# HB-WDS100-C6-O-2_Main_v2p0.net
KiCad netlist of a schematic drawn in EAGLE
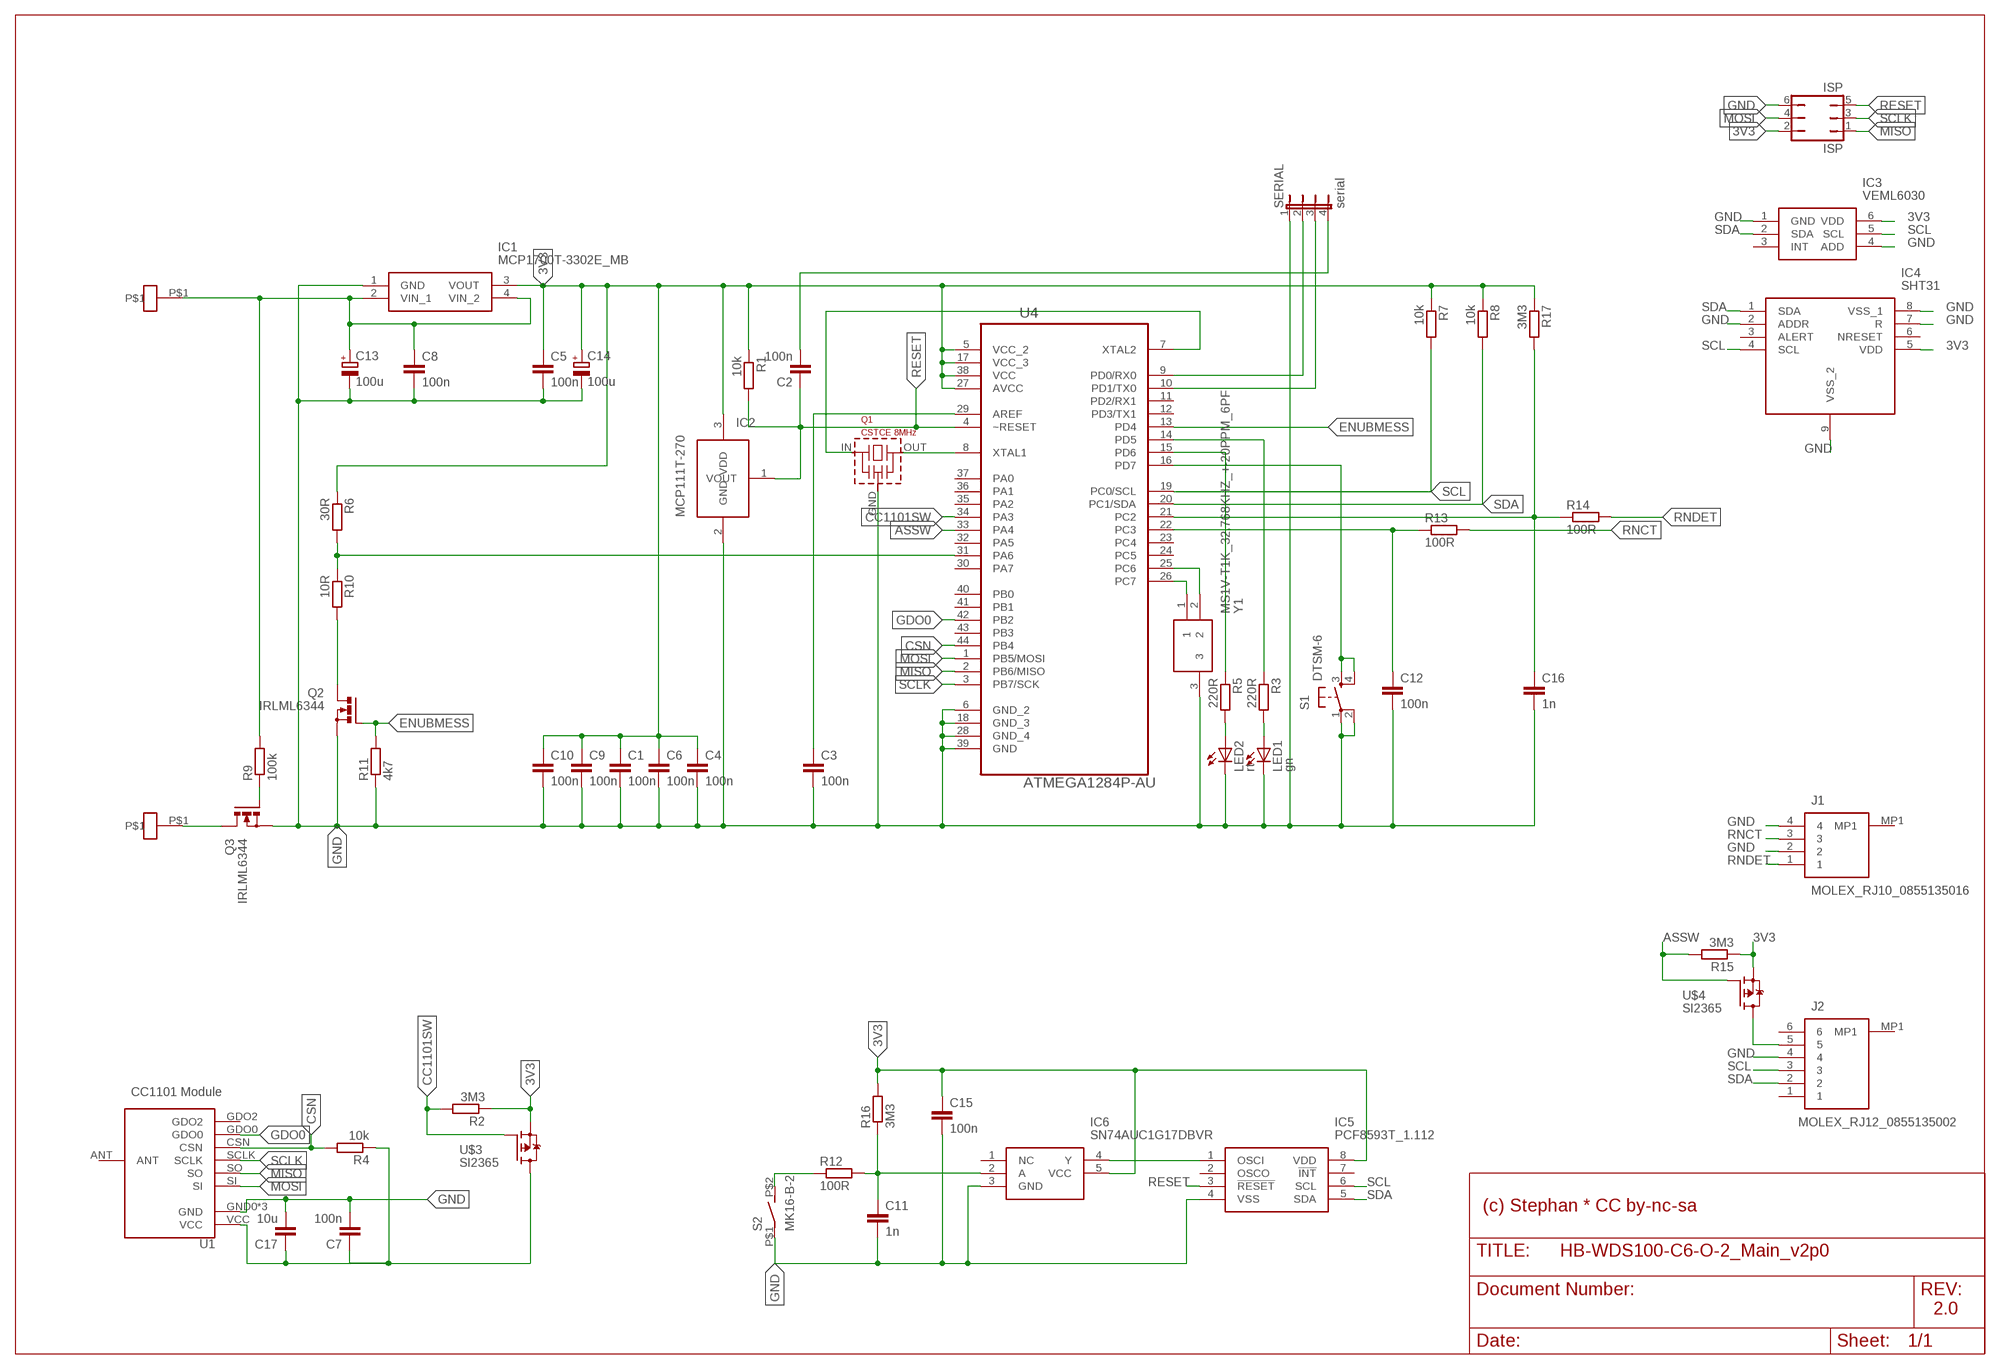
[diagram p0: schematic, sheet 1]

(export (version "E")
  (design (tool "Eeschema 10.0.6"))
  (components
    (comp (ref "C1")
      (value "100n")
      (footprint "eagle-import:C0805K")
      (libsource (lib "eagle-import") (part "resistor_348_C-EUC0805K"))
    )
    (comp (ref "C2")
      (value "100n")
      (footprint "eagle-import:C0805K")
      (libsource (lib "eagle-import") (part "resistor_348_C-EUC0805K"))
    )
    (comp (ref "C3")
      (value "100n")
      (footprint "eagle-import:C0805K")
      (libsource (lib "eagle-import") (part "resistor_348_C-EUC0805K"))
    )
    (comp (ref "C4")
      (value "100n")
      (footprint "eagle-import:C0805K")
      (libsource (lib "eagle-import") (part "resistor_348_C-EUC0805K"))
    )
    (comp (ref "C5")
      (value "100n")
      (footprint "eagle-import:C0805K")
      (libsource (lib "eagle-import") (part "C-EUC0805K"))
    )
    (comp (ref "C6")
      (value "100n")
      (footprint "eagle-import:C0805K")
      (libsource (lib "eagle-import") (part "resistor_348_C-EUC0805K"))
    )
    (comp (ref "C7")
      (value "100n")
      (footprint "eagle-import:C0805K")
      (libsource (lib "eagle-import") (part "resistor_348_C-EUC0805K"))
    )
    (comp (ref "C8")
      (value "100n")
      (footprint "eagle-import:C0805K")
      (libsource (lib "eagle-import") (part "C-EUC0805K"))
    )
    (comp (ref "C9")
      (value "100n")
      (footprint "eagle-import:C0805K")
      (libsource (lib "eagle-import") (part "resistor_348_C-EUC0805K"))
    )
    (comp (ref "C10")
      (value "100n")
      (footprint "eagle-import:C0805K")
      (libsource (lib "eagle-import") (part "resistor_348_C-EUC0805K"))
    )
    (comp (ref "C11")
      (value "1n")
      (footprint "eagle-import:C0805K")
      (libsource (lib "eagle-import") (part "resistor_348_C-EUC0805K"))
    )
    (comp (ref "C12")
      (value "100n")
      (footprint "eagle-import:C0805K")
      (libsource (lib "eagle-import") (part "resistor_348_C-EUC0805K"))
    )
    (comp (ref "C13")
      (value "100u")
      (footprint "eagle-import:CT3528")
      (libsource (lib "eagle-import") (part "CPOL-EUCT3528"))
    )
    (comp (ref "C14")
      (value "100u")
      (footprint "eagle-import:CT3528")
      (libsource (lib "eagle-import") (part "CPOL-EUCT3528"))
    )
    (comp (ref "C15")
      (value "100n")
      (footprint "eagle-import:C0805K")
      (libsource (lib "eagle-import") (part "resistor_348_C-EUC0805K"))
    )
    (comp (ref "C16")
      (value "1n")
      (footprint "eagle-import:C0805K")
      (libsource (lib "eagle-import") (part "resistor_348_C-EUC0805K"))
    )
    (comp (ref "C17")
      (value "10u")
      (footprint "eagle-import:C0805K")
      (libsource (lib "eagle-import") (part "resistor_348_C-EUC0805K"))
    )
    (comp (ref "IC1")
      (value "MCP1700T-3302E_MB")
      (footprint "eagle-import:MCP1700T-3302E_MB")
      (fields
        (field (name "ARROW_PART_NUMBER") "MCP1700T-3302E/MB")
        (field (name "MOUSER_PART_NUMBER") "579-MCP1700T3302E/MB")
      )
      (libsource (lib "eagle-import") (part "MCP1700T-3302E_MB"))
    )
    (comp (ref "IC2")
      (value "MCP111-270")
      (footprint "eagle-import:SOT23")
      (libsource (lib "eagle-import") (part "MCP111T"))
    )
    (comp (ref "IC3")
      (value "VEML6030")
      (footprint "eagle-import:VEML6030-HANDSOLD")
      (fields (field (name "MOUSER_PART_NUMBER") "78-VEML6030"))
      (libsource (lib "eagle-import") (part "VEML6030-HANDSOLD"))
    )
    (comp (ref "IC4")
      (value "SHT31")
      (footprint "eagle-import:SON50P250X250X90-9N-HANDSOLD")
      (fields
        (field (name "ARROW_PART_NUMBER") "SHT31-DIS-F2.5KS")
        (field (name "MANUFACTURER_PART_NUMBER") "SHT31-DIS-F2.5kS")
        (field (name "MOUSER_PART_NUMBER") "403-SHT31-DIS-F")
      )
      (libsource (lib "eagle-import") (part "SHT31-HANDSOLD"))
    )
    (comp (ref "IC5")
      (value "PCF8593T_1.112")
      (footprint "eagle-import:SOIC127P600X175-8N")
      (fields (field (name "MANUFACTURER_PART_NUMBER") "PCF8593T/1.112"))
      (libsource (lib "eagle-import") (part "PCF8593T_1.112"))
    )
    (comp (ref "IC6")
      (value "SN74AUC1G17DBVR")
      (footprint "eagle-import:SOT95P280X145-5N")
      (fields (field (name "MOUSER_PART_NUMBER") "595-SN74AUC1G17DBVR"))
      (libsource (lib "eagle-import") (part "SN74AUC1G17DBVR"))
    )
    (comp (ref "ISP")
      (value "ISP")
      (footprint "eagle-import:JP3Q")
      (libsource (lib "eagle-import") (part "JP3Q"))
    )
    (comp (ref "J1")
      (value "MOLEX_RJ10_0855135016")
      (footprint "eagle-import:MOLEX_RJ10_0855135016")
      (libsource (lib "eagle-import") (part "MOLEX_RJ10_0855135016"))
    )
    (comp (ref "J2")
      (value "MOLEX_RJ12_0855135002")
      (footprint "eagle-import:MOLEX_RJ12_0855135002")
      (fields (field (name "ARROW_PART_NUMBER") "0855135002"))
      (libsource (lib "eagle-import") (part "MOLEX_RJ12_0855135002"))
    )
    (comp (ref "LED1")
      (value "gn")
      (footprint "eagle-import:CHIPLED_0805")
      (libsource (lib "eagle-import") (part "LEDCHIPLED_0805"))
    )
    (comp (ref "LED2")
      (value "rt")
      (footprint "eagle-import:CHIPLED_0805")
      (libsource (lib "eagle-import") (part "LEDCHIPLED_0805"))
    )
    (comp (ref "Q1")
      (value "CSTCE 8MHz")
      (footprint "eagle-import:CSTCE")
      (libsource (lib "eagle-import") (part "CSTCE"))
    )
    (comp (ref "Q2")
      (value "IRLML6344")
      (footprint "eagle-import:SOT-23")
      (libsource (lib "eagle-import") (part "IRLML6344"))
    )
    (comp (ref "Q3")
      (value "IRLML6344")
      (footprint "eagle-import:SOT-23")
      (libsource (lib "eagle-import") (part "IRLML6344"))
    )
    (comp (ref "R1")
      (value "10k")
      (footprint "eagle-import:R0805W")
      (libsource (lib "eagle-import") (part "R-EU_R0805W"))
    )
    (comp (ref "R2")
      (value "3M3")
      (footprint "eagle-import:R0805W")
      (libsource (lib "eagle-import") (part "R-EU_R0805W"))
    )
    (comp (ref "R3")
      (value "220R")
      (footprint "eagle-import:R0805W")
      (libsource (lib "eagle-import") (part "R-EU_R0805W"))
    )
    (comp (ref "R4")
      (value "10k")
      (footprint "eagle-import:R0805W")
      (libsource (lib "eagle-import") (part "R-EU_R0805W"))
    )
    (comp (ref "R5")
      (value "220R")
      (footprint "eagle-import:R0805W")
      (libsource (lib "eagle-import") (part "R-EU_R0805W"))
    )
    (comp (ref "R6")
      (value "30R")
      (footprint "eagle-import:R0805W")
      (libsource (lib "eagle-import") (part "R-EU_R0805W"))
    )
    (comp (ref "R7")
      (value "10k")
      (footprint "eagle-import:R0805W")
      (libsource (lib "eagle-import") (part "R-EU_R0805W"))
    )
    (comp (ref "R8")
      (value "10k")
      (footprint "eagle-import:R0805W")
      (libsource (lib "eagle-import") (part "R-EU_R0805W"))
    )
    (comp (ref "R9")
      (value "100k")
      (footprint "eagle-import:R0805W")
      (libsource (lib "eagle-import") (part "R-EU_R0805W"))
    )
    (comp (ref "R10")
      (value "10R")
      (footprint "eagle-import:R0805W")
      (libsource (lib "eagle-import") (part "R-EU_R0805W"))
    )
    (comp (ref "R11")
      (value "4k7")
      (footprint "eagle-import:R0805W")
      (libsource (lib "eagle-import") (part "R-EU_R0805W"))
    )
    (comp (ref "R12")
      (value "100R")
      (footprint "eagle-import:R0805W")
      (libsource (lib "eagle-import") (part "R-EU_R0805W"))
    )
    (comp (ref "R13")
      (value "100R")
      (footprint "eagle-import:R0805W")
      (libsource (lib "eagle-import") (part "R-EU_R0805W"))
    )
    (comp (ref "R14")
      (value "100R")
      (footprint "eagle-import:R0805W")
      (libsource (lib "eagle-import") (part "R-EU_R0805W"))
    )
    (comp (ref "R15")
      (value "3M3")
      (footprint "eagle-import:R0805W")
      (libsource (lib "eagle-import") (part "R-EU_R0805W"))
    )
    (comp (ref "R16")
      (value "3M3")
      (footprint "eagle-import:R0805W")
      (libsource (lib "eagle-import") (part "R-EU_R0805W"))
    )
    (comp (ref "R17")
      (value "3M3")
      (footprint "eagle-import:R0805W")
      (libsource (lib "eagle-import") (part "R-EU_R0805W"))
    )
    (comp (ref "S1")
      (value "DTSM-6")
      (footprint "eagle-import:DTSM-6")
      (libsource (lib "eagle-import") (part "DTSM-6"))
    )
    (comp (ref "S2")
      (value "MK16-B-2")
      (footprint "eagle-import:MK16-B-2")
      (libsource (lib "eagle-import") (part "MK16-B-2"))
    )
    (comp (ref "SERIAL")
      (value "serial")
      (footprint "eagle-import:JP4")
      (libsource (lib "eagle-import") (part "JP4E"))
    )
    (comp (ref "U$1")
      (value "LOETOESE")
      (footprint "eagle-import:LOETOESE")
      (libsource (lib "eagle-import") (part "LOETOESE"))
    )
    (comp (ref "U$2")
      (value "LOETOESE")
      (footprint "eagle-import:LOETOESE")
      (libsource (lib "eagle-import") (part "LOETOESE"))
    )
    (comp (ref "U$3")
      (value "SI2365")
      (footprint "eagle-import:SOT23")
      (libsource (lib "eagle-import") (part "SI2323"))
    )
    (comp (ref "U$4")
      (value "SI2365")
      (footprint "eagle-import:SOT23")
      (libsource (lib "eagle-import") (part "SI2323"))
    )
    (comp (ref "U1")
      (value "CC1101CC1101-SMD-2MM")
      (footprint "eagle-import:CC1101-SMD2MM")
      (libsource (lib "eagle-import") (part "CC1101CC1101-SMD-2MM"))
    )
    (comp (ref "U4")
      (value "ATMEGA1284P-AU")
      (footprint "eagle-import:QFP80P1200X1200X120-44N")
      (libsource (lib "eagle-import") (part "ATMEGA1284P-AU"))
    )
    (comp (ref "Y1")
      (value "MS1V-T1K_32.768KHZ_+-20PPM_6PF")
      (footprint "eagle-import:MS1VT1K32768KHZ20PPM6PF")
      (fields (field (name "MANUFACTURER_PART_NUMBER") "MS1V-T1K 32.768KHZ +-20PPM 6PF"))
      (libsource (lib "eagle-import") (part "MS1V-T1K_32.768KHZ_+-20PPM_6PF"))
    )
  )
  (nets
    (net (code "1") (name "3V3") (class "Default")
      (node (ref "C1") (pin "1") (pinfunction "1_1") (pintype "passive"))
      (node (ref "C10") (pin "1") (pinfunction "1_1") (pintype "passive"))
      (node (ref "C14") (pin "+") (pinfunction "+_+") (pintype "passive"))
      (node (ref "C15") (pin "1") (pinfunction "1_1") (pintype "passive"))
      (node (ref "C4") (pin "1") (pinfunction "1_1") (pintype "passive"))
      (node (ref "C5") (pin "1") (pinfunction "1_1") (pintype "passive"))
      (node (ref "C6") (pin "1") (pinfunction "1_1") (pintype "passive"))
      (node (ref "C9") (pin "1") (pinfunction "1_1") (pintype "passive"))
      (node (ref "IC1") (pin "3") (pinfunction "VOUT_3") (pintype "output"))
      (node (ref "IC2") (pin "3") (pinfunction "VDD_3") (pintype "power_in"))
      (node (ref "IC3") (pin "6") (pinfunction "VDD_6") (pintype "bidirectional"))
      (node (ref "IC4") (pin "5") (pinfunction "VDD_5") (pintype "power_in"))
      (node (ref "IC5") (pin "8") (pinfunction "VDD_8") (pintype "bidirectional"))
      (node (ref "IC6") (pin "5") (pinfunction "VCC_5") (pintype "power_in"))
      (node (ref "ISP") (pin "2") (pinfunction "2_2") (pintype "passive"))
      (node (ref "R1") (pin "1") (pinfunction "1_1") (pintype "passive"))
      (node (ref "R15") (pin "1") (pinfunction "1_1") (pintype "passive"))
      (node (ref "R16") (pin "2") (pinfunction "2_2") (pintype "passive"))
      (node (ref "R17") (pin "1") (pinfunction "1_1") (pintype "passive"))
      (node (ref "R2") (pin "1") (pinfunction "1_1") (pintype "passive"))
      (node (ref "R6") (pin "1") (pinfunction "1_1") (pintype "passive"))
      (node (ref "R7") (pin "1") (pinfunction "1_1") (pintype "passive"))
      (node (ref "R8") (pin "1") (pinfunction "1_1") (pintype "passive"))
      (node (ref "U$3") (pin "2") (pinfunction "S_2") (pintype "passive"))
      (node (ref "U$4") (pin "2") (pinfunction "S_2") (pintype "passive"))
      (node (ref "U4") (pin "17") (pinfunction "VCC_3_17") (pintype "power_in"))
      (node (ref "U4") (pin "27") (pinfunction "AVCC_27") (pintype "power_in"))
      (node (ref "U4") (pin "38") (pinfunction "VCC_38") (pintype "power_in"))
      (node (ref "U4") (pin "5") (pinfunction "VCC_2_5") (pintype "power_in"))
    )
    (net (code "2") (name "ASSW") (class "Default")
      (node (ref "R15") (pin "2") (pinfunction "2_2") (pintype "passive"))
      (node (ref "U$4") (pin "1") (pinfunction "G_1") (pintype "passive"))
      (node (ref "U4") (pin "33") (pinfunction "PA4_33") (pintype "bidirectional"))
    )
    (net (code "3") (name "CC1101SW") (class "Default")
      (node (ref "R2") (pin "2") (pinfunction "2_2") (pintype "passive"))
      (node (ref "U$3") (pin "1") (pinfunction "G_1") (pintype "passive"))
      (node (ref "U4") (pin "34") (pinfunction "PA3_34") (pintype "bidirectional"))
    )
    (net (code "4") (name "CSN") (class "Default")
      (node (ref "R4") (pin "2") (pinfunction "2_2") (pintype "passive"))
      (node (ref "U1") (pin "CSN") (pinfunction "CSN_CSN") (pintype "bidirectional"))
      (node (ref "U4") (pin "44") (pinfunction "PB4_44") (pintype "bidirectional"))
    )
    (net (code "5") (name "ENUBMESS") (class "Default")
      (node (ref "Q2") (pin "P1") (pinfunction "G_P1") (pintype "passive"))
      (node (ref "R11") (pin "2") (pinfunction "2_2") (pintype "passive"))
      (node (ref "U4") (pin "13") (pinfunction "PD4_13") (pintype "bidirectional"))
    )
    (net (code "6") (name "GDO0") (class "Default")
      (node (ref "U1") (pin "GDO0") (pinfunction "GDO0_GDO0") (pintype "output"))
      (node (ref "U4") (pin "42") (pinfunction "PB2_42") (pintype "bidirectional"))
    )
    (net (code "7") (name "GND") (class "Default")
      (node (ref "C1") (pin "2") (pinfunction "2_2") (pintype "passive"))
      (node (ref "C10") (pin "2") (pinfunction "2_2") (pintype "passive"))
      (node (ref "C11") (pin "2") (pinfunction "2_2") (pintype "passive"))
      (node (ref "C12") (pin "2") (pinfunction "2_2") (pintype "passive"))
      (node (ref "C13") (pin "-") (pinfunction "-_-") (pintype "passive"))
      (node (ref "C14") (pin "-") (pinfunction "-_-") (pintype "passive"))
      (node (ref "C15") (pin "2") (pinfunction "2_2") (pintype "passive"))
      (node (ref "C16") (pin "2") (pinfunction "2_2") (pintype "passive"))
      (node (ref "C17") (pin "2") (pinfunction "2_2") (pintype "passive"))
      (node (ref "C3") (pin "2") (pinfunction "2_2") (pintype "passive"))
      (node (ref "C4") (pin "2") (pinfunction "2_2") (pintype "passive"))
      (node (ref "C5") (pin "2") (pinfunction "2_2") (pintype "passive"))
      (node (ref "C6") (pin "2") (pinfunction "2_2") (pintype "passive"))
      (node (ref "C7") (pin "2") (pinfunction "2_2") (pintype "passive"))
      (node (ref "C8") (pin "2") (pinfunction "2_2") (pintype "passive"))
      (node (ref "C9") (pin "2") (pinfunction "2_2") (pintype "passive"))
      (node (ref "IC1") (pin "1") (pinfunction "GND_1") (pintype "power_in"))
      (node (ref "IC2") (pin "2") (pinfunction "GND_2") (pintype "power_in"))
      (node (ref "IC3") (pin "1") (pinfunction "GND_1") (pintype "bidirectional"))
      (node (ref "IC3") (pin "4") (pinfunction "ADD_4") (pintype "bidirectional"))
      (node (ref "IC4") (pin "2") (pinfunction "ADDR_2") (pintype "input"))
      (node (ref "IC4") (pin "7") (pinfunction "R_7") (pintype "bidirectional"))
      (node (ref "IC4") (pin "8") (pinfunction "VSS_1_8") (pintype "power_in"))
      (node (ref "IC4") (pin "9") (pinfunction "VSS_2_9") (pintype "power_in"))
      (node (ref "IC5") (pin "4") (pinfunction "VSS_4") (pintype "bidirectional"))
      (node (ref "IC6") (pin "3") (pinfunction "GND_3") (pintype "power_in"))
      (node (ref "ISP") (pin "6") (pinfunction "6_6") (pintype "passive"))
      (node (ref "J1") (pin "2") (pinfunction "2_2") (pintype "bidirectional"))
      (node (ref "J1") (pin "4") (pinfunction "4_4") (pintype "bidirectional"))
      (node (ref "J2") (pin "4") (pinfunction "4_4") (pintype "bidirectional"))
      (node (ref "LED1") (pin "C") (pinfunction "C_C") (pintype "passive"))
      (node (ref "LED2") (pin "C") (pinfunction "C_C") (pintype "passive"))
      (node (ref "Q1") (pin "GND") (pinfunction "GND_GND") (pintype "power_in"))
      (node (ref "Q2") (pin "P2") (pinfunction "S_P2") (pintype "passive"))
      (node (ref "Q3") (pin "P2") (pinfunction "S_P2") (pintype "passive"))
      (node (ref "R11") (pin "1") (pinfunction "1_1") (pintype "passive"))
      (node (ref "S1") (pin "1") (pinfunction "1_1") (pintype "passive"))
      (node (ref "S1") (pin "2") (pinfunction "2_2") (pintype "passive"))
      (node (ref "S2") (pin "P$1") (pinfunction "P_P$1") (pintype "passive"))
      (node (ref "SERIAL") (pin "1") (pinfunction "1_1") (pintype "passive"))
      (node (ref "U1") (pin "GND0") (pinfunction "GND_GND0") (pintype "power_in"))
      (node (ref "U1") (pin "GND1") (pinfunction "GND_GND1") (pintype "power_in"))
      (node (ref "U1") (pin "GND2") (pinfunction "GND_GND2") (pintype "power_in"))
      (node (ref "U4") (pin "18") (pinfunction "GND_3_18") (pintype "passive"))
      (node (ref "U4") (pin "28") (pinfunction "GND_4_28") (pintype "passive"))
      (node (ref "U4") (pin "39") (pinfunction "GND_39") (pintype "passive"))
      (node (ref "U4") (pin "6") (pinfunction "GND_2_6") (pintype "passive"))
      (node (ref "Y1") (pin "3") (pinfunction "3_3") (pintype "bidirectional"))
    )
    (net (code "8") (name "MISO") (class "Default")
      (node (ref "ISP") (pin "1") (pinfunction "1_1") (pintype "passive"))
      (node (ref "U1") (pin "SO") (pinfunction "SO_SO") (pintype "output"))
      (node (ref "U4") (pin "2") (pinfunction "PB6/MISO_2") (pintype "bidirectional"))
    )
    (net (code "9") (name "MOSI") (class "Default")
      (node (ref "ISP") (pin "4") (pinfunction "4_4") (pintype "passive"))
      (node (ref "U1") (pin "SI") (pinfunction "SI_SI") (pintype "input"))
      (node (ref "U4") (pin "1") (pinfunction "PB5/MOSI_1") (pintype "bidirectional"))
    )
    (net (code "10") (name "Net-(C2-Pad2)") (class "Default")
      (node (ref "C2") (pin "2") (pinfunction "2_2") (pintype "passive"))
      (node (ref "SERIAL") (pin "4") (pinfunction "4_4") (pintype "passive"))
    )
    (net (code "11") (name "Net-(IC1-VIN_1)") (class "Default")
      (node (ref "C13") (pin "+") (pinfunction "+_+") (pintype "passive"))
      (node (ref "C8") (pin "1") (pinfunction "1_1") (pintype "passive"))
      (node (ref "IC1") (pin "2") (pinfunction "VIN_1_2") (pintype "input"))
      (node (ref "IC1") (pin "4") (pinfunction "VIN_2_4") (pintype "bidirectional"))
      (node (ref "R9") (pin "2") (pinfunction "2_2") (pintype "passive"))
      (node (ref "U$1") (pin "P$1") (pinfunction "P$1_P$1") (pintype "bidirectional"))
    )
    (net (code "12") (name "Net-(IC5-OSCI)") (class "Default")
      (node (ref "IC5") (pin "1") (pinfunction "OSCI_1") (pintype "bidirectional"))
      (node (ref "IC6") (pin "4") (pinfunction "Y_4") (pintype "output"))
    )
    (net (code "13") (name "Net-(IC6-A)") (class "Default")
      (node (ref "C11") (pin "1") (pinfunction "1_1") (pintype "passive"))
      (node (ref "IC6") (pin "2") (pinfunction "A_2") (pintype "input"))
      (node (ref "R12") (pin "2") (pinfunction "2_2") (pintype "passive"))
      (node (ref "R16") (pin "1") (pinfunction "1_1") (pintype "passive"))
    )
    (net (code "14") (name "Net-(LED1-PadA)") (class "Default")
      (node (ref "LED1") (pin "A") (pinfunction "A_A") (pintype "passive"))
      (node (ref "R3") (pin "2") (pinfunction "2_2") (pintype "passive"))
    )
    (net (code "15") (name "Net-(LED2-PadA)") (class "Default")
      (node (ref "LED2") (pin "A") (pinfunction "A_A") (pintype "passive"))
      (node (ref "R5") (pin "2") (pinfunction "2_2") (pintype "passive"))
    )
    (net (code "16") (name "Net-(Q2-D)") (class "Default")
      (node (ref "Q2") (pin "P3") (pinfunction "D_P3") (pintype "passive"))
      (node (ref "R10") (pin "2") (pinfunction "2_2") (pintype "passive"))
    )
    (net (code "17") (name "Net-(Q3-D)") (class "Default")
      (node (ref "Q3") (pin "P3") (pinfunction "D_P3") (pintype "passive"))
      (node (ref "U$2") (pin "P$1") (pinfunction "P$1_P$1") (pintype "bidirectional"))
    )
    (net (code "18") (name "Net-(Q3-G)") (class "Default")
      (node (ref "Q3") (pin "P1") (pinfunction "G_P1") (pintype "passive"))
      (node (ref "R9") (pin "1") (pinfunction "1_1") (pintype "passive"))
    )
    (net (code "19") (name "Net-(S2-S)") (class "Default")
      (node (ref "R12") (pin "1") (pinfunction "1_1") (pintype "passive"))
      (node (ref "S2") (pin "P$2") (pinfunction "S_P$2") (pintype "passive"))
    )
    (net (code "20") (name "Net-(U$3-D)") (class "Default")
      (node (ref "C17") (pin "1") (pinfunction "1_1") (pintype "passive"))
      (node (ref "C7") (pin "1") (pinfunction "1_1") (pintype "passive"))
      (node (ref "R4") (pin "1") (pinfunction "1_1") (pintype "passive"))
      (node (ref "U$3") (pin "3") (pinfunction "D_3") (pintype "passive"))
      (node (ref "U1") (pin "VCC") (pinfunction "VCC_VCC") (pintype "power_in"))
    )
    (net (code "21") (name "Net-(U$4-D)") (class "Default")
      (node (ref "J2") (pin "5") (pinfunction "5_5") (pintype "bidirectional"))
      (node (ref "U$4") (pin "3") (pinfunction "D_3") (pintype "passive"))
    )
    (net (code "22") (name "Net-(U4-AREF)") (class "Default")
      (node (ref "C3") (pin "1") (pinfunction "1_1") (pintype "passive"))
      (node (ref "U4") (pin "29") (pinfunction "AREF_29") (pintype "input"))
    )
    (net (code "23") (name "Net-(U4-PA6)") (class "Default")
      (node (ref "R10") (pin "1") (pinfunction "1_1") (pintype "passive"))
      (node (ref "R6") (pin "2") (pinfunction "2_2") (pintype "passive"))
      (node (ref "U4") (pin "31") (pinfunction "PA6_31") (pintype "bidirectional"))
    )
    (net (code "24") (name "Net-(U4-PC2)") (class "Default")
      (node (ref "C16") (pin "1") (pinfunction "1_1") (pintype "passive"))
      (node (ref "R14") (pin "1") (pinfunction "1_1") (pintype "passive"))
      (node (ref "R17") (pin "2") (pinfunction "2_2") (pintype "passive"))
      (node (ref "U4") (pin "21") (pinfunction "PC2_21") (pintype "bidirectional"))
    )
    (net (code "25") (name "Net-(U4-PC3)") (class "Default")
      (node (ref "C12") (pin "1") (pinfunction "1_1") (pintype "passive"))
      (node (ref "R13") (pin "1") (pinfunction "1_1") (pintype "passive"))
      (node (ref "U4") (pin "22") (pinfunction "PC3_22") (pintype "bidirectional"))
    )
    (net (code "26") (name "Net-(U4-PC6)") (class "Default")
      (node (ref "U4") (pin "25") (pinfunction "PC6_25") (pintype "bidirectional"))
      (node (ref "Y1") (pin "2") (pinfunction "2_2") (pintype "bidirectional"))
    )
    (net (code "27") (name "Net-(U4-PC7)") (class "Default")
      (node (ref "U4") (pin "26") (pinfunction "PC7_26") (pintype "bidirectional"))
      (node (ref "Y1") (pin "1") (pinfunction "1_1") (pintype "bidirectional"))
    )
    (net (code "28") (name "Net-(U4-PD0{slash}RX0)") (class "Default")
      (node (ref "SERIAL") (pin "2") (pinfunction "2_2") (pintype "passive"))
      (node (ref "U4") (pin "9") (pinfunction "PD0/RX0_9") (pintype "bidirectional"))
    )
    (net (code "29") (name "Net-(U4-PD1{slash}TX0)") (class "Default")
      (node (ref "SERIAL") (pin "3") (pinfunction "3_3") (pintype "passive"))
      (node (ref "U4") (pin "10") (pinfunction "PD1/TX0_10") (pintype "bidirectional"))
    )
    (net (code "30") (name "Net-(U4-PD5)") (class "Default")
      (node (ref "R3") (pin "1") (pinfunction "1_1") (pintype "passive"))
      (node (ref "U4") (pin "14") (pinfunction "PD5_14") (pintype "bidirectional"))
    )
    (net (code "31") (name "Net-(U4-PD6)") (class "Default")
      (node (ref "R5") (pin "1") (pinfunction "1_1") (pintype "passive"))
      (node (ref "U4") (pin "15") (pinfunction "PD6_15") (pintype "bidirectional"))
    )
    (net (code "32") (name "Net-(U4-PD7)") (class "Default")
      (node (ref "S1") (pin "3") (pinfunction "3_3") (pintype "passive"))
      (node (ref "S1") (pin "4") (pinfunction "4_4") (pintype "passive"))
      (node (ref "U4") (pin "16") (pinfunction "PD7_16") (pintype "bidirectional"))
    )
    (net (code "33") (name "Net-(U4-XTAL1)") (class "Default")
      (node (ref "Q1") (pin "OUT") (pinfunction "OUT_OUT") (pintype "output"))
      (node (ref "U4") (pin "8") (pinfunction "XTAL1_8") (pintype "input"))
    )
    (net (code "34") (name "Net-(U4-XTAL2)") (class "Default")
      (node (ref "Q1") (pin "IN") (pinfunction "IN_IN") (pintype "input"))
      (node (ref "U4") (pin "7") (pinfunction "XTAL2_7") (pintype "output"))
    )
    (net (code "35") (name "RESET") (class "Default")
      (node (ref "C2") (pin "1") (pinfunction "1_1") (pintype "passive"))
      (node (ref "IC2") (pin "1") (pinfunction "VOUT_1") (pintype "output"))
      (node (ref "IC5") (pin "3") (pinfunction "~{RESET}_3") (pintype "bidirectional"))
      (node (ref "ISP") (pin "5") (pinfunction "5_5") (pintype "passive"))
      (node (ref "R1") (pin "2") (pinfunction "2_2") (pintype "passive"))
      (node (ref "U4") (pin "4") (pinfunction "~{RESET}_4") (pintype "input"))
    )
    (net (code "36") (name "RNCT") (class "Default")
      (node (ref "J1") (pin "3") (pinfunction "3_3") (pintype "bidirectional"))
      (node (ref "R13") (pin "2") (pinfunction "2_2") (pintype "passive"))
    )
    (net (code "37") (name "RNDET") (class "Default")
      (node (ref "J1") (pin "1") (pinfunction "1_1") (pintype "bidirectional"))
      (node (ref "R14") (pin "2") (pinfunction "2_2") (pintype "passive"))
    )
    (net (code "38") (name "SCL") (class "Default")
      (node (ref "IC3") (pin "5") (pinfunction "SCL_5") (pintype "bidirectional"))
      (node (ref "IC4") (pin "4") (pinfunction "SCL_4") (pintype "bidirectional"))
      (node (ref "IC5") (pin "6") (pinfunction "SCL_6") (pintype "bidirectional"))
      (node (ref "J2") (pin "3") (pinfunction "3_3") (pintype "bidirectional"))
      (node (ref "R7") (pin "2") (pinfunction "2_2") (pintype "passive"))
      (node (ref "U4") (pin "19") (pinfunction "PC0/SCL_19") (pintype "bidirectional"))
    )
    (net (code "39") (name "SCLK") (class "Default")
      (node (ref "ISP") (pin "3") (pinfunction "3_3") (pintype "passive"))
      (node (ref "U1") (pin "SCLK") (pinfunction "SCLK_SCLK") (pintype "input"))
      (node (ref "U4") (pin "3") (pinfunction "PB7/SCK_3") (pintype "bidirectional"))
    )
    (net (code "40") (name "SDA") (class "Default")
      (node (ref "IC3") (pin "2") (pinfunction "SDA_2") (pintype "bidirectional"))
      (node (ref "IC4") (pin "1") (pinfunction "SDA_1") (pintype "bidirectional"))
      (node (ref "IC5") (pin "5") (pinfunction "SDA_5") (pintype "bidirectional"))
      (node (ref "J2") (pin "2") (pinfunction "2_2") (pintype "bidirectional"))
      (node (ref "R8") (pin "2") (pinfunction "2_2") (pintype "passive"))
      (node (ref "U4") (pin "20") (pinfunction "PC1/SDA_20") (pintype "bidirectional"))
    )
    (net (code "41") (name "unconnected-(IC3-INT-Pad3)") (class "Default")
      (node (ref "IC3") (pin "3") (pinfunction "INT_3") (pintype "bidirectional"))
    )
    (net (code "42") (name "unconnected-(IC4-ALERT-Pad3)") (class "Default")
      (node (ref "IC4") (pin "3") (pinfunction "ALERT_3") (pintype "output"))
    )
    (net (code "43") (name "unconnected-(IC4-NRESET-Pad6)") (class "Default")
      (node (ref "IC4") (pin "6") (pinfunction "NRESET_6") (pintype "input"))
    )
    (net (code "44") (name "unconnected-(IC5-OSCO-Pad2)") (class "Default")
      (node (ref "IC5") (pin "2") (pinfunction "OSCO_2") (pintype "bidirectional"))
    )
    (net (code "45") (name "unconnected-(IC5-~{INT}-Pad7)") (class "Default")
      (node (ref "IC5") (pin "7") (pinfunction "~{INT}_7") (pintype "bidirectional"))
    )
    (net (code "46") (name "unconnected-(IC6-NC-Pad1)") (class "Default")
      (node (ref "IC6") (pin "1") (pinfunction "NC_1") (pintype "no_connect"))
    )
    (net (code "47") (name "unconnected-(J1-PadMP1)") (class "Default")
      (node (ref "J1") (pin "MP1") (pinfunction "MP1_MP1") (pintype "bidirectional"))
    )
    (net (code "48") (name "unconnected-(J2-Pad1)") (class "Default")
      (node (ref "J2") (pin "1") (pinfunction "1_1") (pintype "bidirectional"))
    )
    (net (code "49") (name "unconnected-(J2-Pad6)") (class "Default")
      (node (ref "J2") (pin "6") (pinfunction "6_6") (pintype "bidirectional"))
    )
    (net (code "50") (name "unconnected-(J2-PadMP1)") (class "Default")
      (node (ref "J2") (pin "MP1") (pinfunction "MP1_MP1") (pintype "bidirectional"))
    )
    (net (code "51") (name "unconnected-(U1-PadANT)") (class "Default")
      (node (ref "U1") (pin "ANT") (pinfunction "ANT_ANT") (pintype "input"))
    )
    (net (code "52") (name "unconnected-(U1-PadGDO2)") (class "Default")
      (node (ref "U1") (pin "GDO2") (pinfunction "GDO2_GDO2") (pintype "output"))
    )
    (net (code "53") (name "unconnected-(U4-PA0-Pad37)") (class "Default")
      (node (ref "U4") (pin "37") (pinfunction "PA0_37") (pintype "bidirectional"))
    )
    (net (code "54") (name "unconnected-(U4-PA1-Pad36)") (class "Default")
      (node (ref "U4") (pin "36") (pinfunction "PA1_36") (pintype "bidirectional"))
    )
    (net (code "55") (name "unconnected-(U4-PA2-Pad35)") (class "Default")
      (node (ref "U4") (pin "35") (pinfunction "PA2_35") (pintype "bidirectional"))
    )
    (net (code "56") (name "unconnected-(U4-PA5-Pad32)") (class "Default")
      (node (ref "U4") (pin "32") (pinfunction "PA5_32") (pintype "bidirectional"))
    )
    (net (code "57") (name "unconnected-(U4-PA7-Pad30)") (class "Default")
      (node (ref "U4") (pin "30") (pinfunction "PA7_30") (pintype "bidirectional"))
    )
    (net (code "58") (name "unconnected-(U4-PB0-Pad40)") (class "Default")
      (node (ref "U4") (pin "40") (pinfunction "PB0_40") (pintype "bidirectional"))
    )
    (net (code "59") (name "unconnected-(U4-PB1-Pad41)") (class "Default")
      (node (ref "U4") (pin "41") (pinfunction "PB1_41") (pintype "bidirectional"))
    )
    (net (code "60") (name "unconnected-(U4-PB3-Pad43)") (class "Default")
      (node (ref "U4") (pin "43") (pinfunction "PB3_43") (pintype "bidirectional"))
    )
    (net (code "61") (name "unconnected-(U4-PC4-Pad23)") (class "Default")
      (node (ref "U4") (pin "23") (pinfunction "PC4_23") (pintype "bidirectional"))
    )
    (net (code "62") (name "unconnected-(U4-PC5-Pad24)") (class "Default")
      (node (ref "U4") (pin "24") (pinfunction "PC5_24") (pintype "bidirectional"))
    )
    (net (code "63") (name "unconnected-(U4-PD2{slash}RX1-Pad11)") (class "Default")
      (node (ref "U4") (pin "11") (pinfunction "PD2/RX1_11") (pintype "bidirectional"))
    )
    (net (code "64") (name "unconnected-(U4-PD3{slash}TX1-Pad12)") (class "Default")
      (node (ref "U4") (pin "12") (pinfunction "PD3/TX1_12") (pintype "bidirectional"))
    )
  )
)
